# MCU025A_XDS110_MCU.net
KiCad netlist of a schematic drawn in Altium Designer
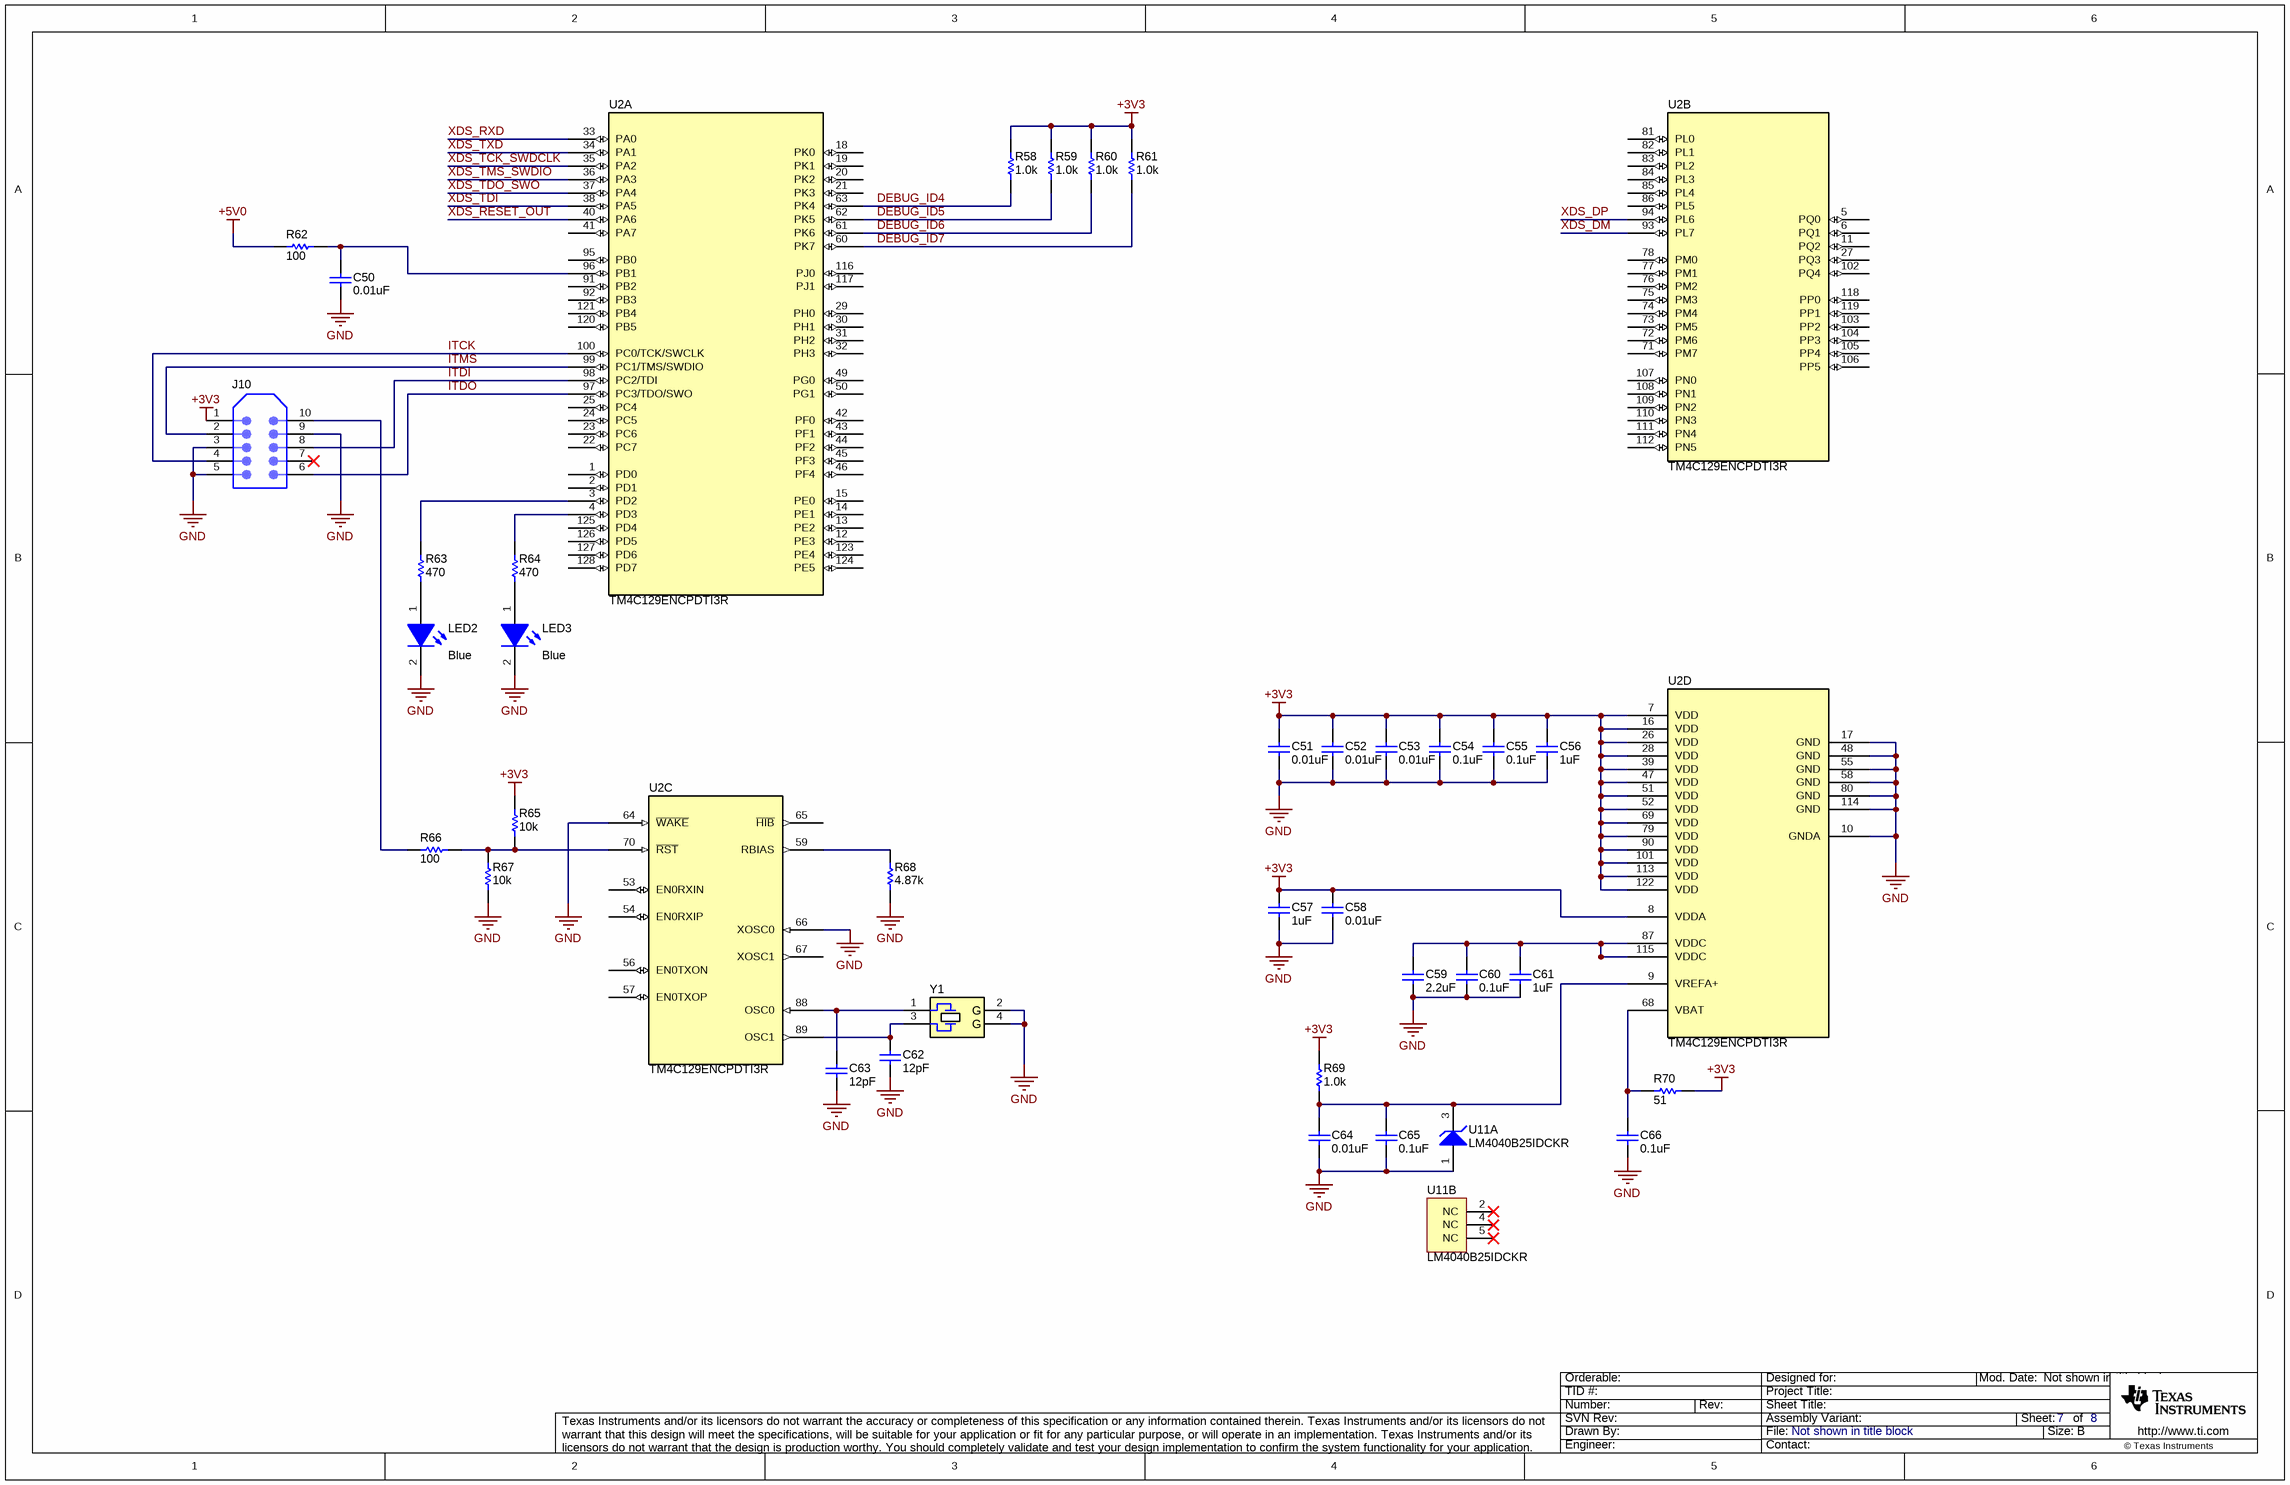
[diagram p0: MCU025A_XDS110_MCU.SchDoc]

(export (version "E")
  (design (tool "Eeschema 10.0.6"))
  (components
    (comp (ref "C50")
      (value "GRM155R71E103KA01D")
      (footprint "0402")
      (description "CAP, CERM, 0.01 uF, 25 V, +/- 10%, X7R, 0402")
      (fields
        (field (name "VALUEDISPLAYED") "0.01uF")
        (field (name "MANUFACTURER") "MuRata")
        (field (name "PUBLISHER") "Texas Instruments")
      )
      (libsource (lib "Altium Vault - TI") (part "Capacitor"))
    )
    (comp (ref "C51")
      (value "GRM155R71E103KA01D")
      (footprint "0402")
      (description "CAP, CERM, 0.01 uF, 25 V, +/- 10%, X7R, 0402")
      (fields
        (field (name "VALUEDISPLAYED") "0.01uF")
        (field (name "MANUFACTURER") "MuRata")
        (field (name "PUBLISHER") "Texas Instruments")
      )
      (libsource (lib "Altium Vault - TI") (part "Capacitor"))
    )
    (comp (ref "C52")
      (value "GRM155R71E103KA01D")
      (footprint "0402")
      (description "CAP, CERM, 0.01 uF, 25 V, +/- 10%, X7R, 0402")
      (fields
        (field (name "VALUEDISPLAYED") "0.01uF")
        (field (name "MANUFACTURER") "MuRata")
        (field (name "PUBLISHER") "Texas Instruments")
      )
      (libsource (lib "Altium Vault - TI") (part "Capacitor"))
    )
    (comp (ref "C53")
      (value "GRM155R71E103KA01D")
      (footprint "0402")
      (description "CAP, CERM, 0.01 uF, 25 V, +/- 10%, X7R, 0402")
      (fields
        (field (name "VALUEDISPLAYED") "0.01uF")
        (field (name "MANUFACTURER") "MuRata")
        (field (name "PUBLISHER") "Texas Instruments")
      )
      (libsource (lib "Altium Vault - TI") (part "Capacitor"))
    )
    (comp (ref "C54")
      (value "GRM155R70J104KA01D")
      (footprint "0402")
      (description "CAP, CERM, 0.1 uF, 6.3 V, +/- 10%, X7R, 0402")
      (fields
        (field (name "VALUEDISPLAYED") "0.1uF")
        (field (name "MANUFACTURER") "MuRata")
        (field (name "PUBLISHER") "Texas Instruments")
      )
      (libsource (lib "Altium Vault - TI") (part "Capacitor"))
    )
    (comp (ref "C55")
      (value "GRM155R70J104KA01D")
      (footprint "0402")
      (description "CAP, CERM, 0.1 uF, 6.3 V, +/- 10%, X7R, 0402")
      (fields
        (field (name "VALUEDISPLAYED") "0.1uF")
        (field (name "MANUFACTURER") "MuRata")
        (field (name "PUBLISHER") "Texas Instruments")
      )
      (libsource (lib "Altium Vault - TI") (part "Capacitor"))
    )
    (comp (ref "C56")
      (value "GRM155R61A105KE15D")
      (footprint "0402")
      (description "CAP, CERM, 1 uF, 10 V, +/- 10%, X5R, 0402")
      (fields
        (field (name "VALUEDISPLAYED") "1uF")
        (field (name "MANUFACTURER") "MuRata")
        (field (name "PUBLISHER") "Texas Instruments")
      )
      (libsource (lib "Altium Vault - TI") (part "Capacitor"))
    )
    (comp (ref "C57")
      (value "GRM155R61A105KE15D")
      (footprint "0402")
      (description "CAP, CERM, 1 uF, 10 V, +/- 10%, X5R, 0402")
      (fields
        (field (name "VALUEDISPLAYED") "1uF")
        (field (name "MANUFACTURER") "MuRata")
        (field (name "PUBLISHER") "Texas Instruments")
      )
      (libsource (lib "Altium Vault - TI") (part "Capacitor"))
    )
    (comp (ref "C58")
      (value "GRM155R71E103KA01D")
      (footprint "0402")
      (description "CAP, CERM, 0.01 uF, 25 V, +/- 10%, X7R, 0402")
      (fields
        (field (name "VALUEDISPLAYED") "0.01uF")
        (field (name "MANUFACTURER") "MuRata")
        (field (name "PUBLISHER") "Texas Instruments")
      )
      (libsource (lib "Altium Vault - TI") (part "Capacitor"))
    )
    (comp (ref "C59")
      (value "GRM155R60J225KE95D")
      (footprint "0402")
      (description "CAP, CERM, 2.2 uF, 6.3 V, +/- 10%, X5R, 0402")
      (fields
        (field (name "VALUEDISPLAYED") "2.2uF")
        (field (name "MANUFACTURER") "MuRata")
        (field (name "PUBLISHER") "Texas Instruments")
      )
      (libsource (lib "Altium Vault - TI") (part "Capacitor"))
    )
    (comp (ref "C60")
      (value "GRM155R70J104KA01D")
      (footprint "0402")
      (description "CAP, CERM, 0.1 uF, 6.3 V, +/- 10%, X7R, 0402")
      (fields
        (field (name "VALUEDISPLAYED") "0.1uF")
        (field (name "MANUFACTURER") "MuRata")
        (field (name "PUBLISHER") "Texas Instruments")
      )
      (libsource (lib "Altium Vault - TI") (part "Capacitor"))
    )
    (comp (ref "C61")
      (value "GRM155R61A105KE15D")
      (footprint "0402")
      (description "CAP, CERM, 1 uF, 10 V, +/- 10%, X5R, 0402")
      (fields
        (field (name "VALUEDISPLAYED") "1uF")
        (field (name "MANUFACTURER") "MuRata")
        (field (name "PUBLISHER") "Texas Instruments")
      )
      (libsource (lib "Altium Vault - TI") (part "Capacitor"))
    )
    (comp (ref "C62")
      (value "GRM1555C1H120JA01D")
      (footprint "0402")
      (description "CAP, CERM, 12 pF, 50 V, +/- 5%, C0G/NP0, 0402")
      (fields
        (field (name "VALUEDISPLAYED") "12pF")
        (field (name "MANUFACTURER") "MuRata")
        (field (name "PUBLISHER") "Texas Instruments")
      )
      (libsource (lib "Altium Vault - TI") (part "Capacitor"))
    )
    (comp (ref "C63")
      (value "GRM1555C1H120JA01D")
      (footprint "0402")
      (description "CAP, CERM, 12 pF, 50 V, +/- 5%, C0G/NP0, 0402")
      (fields
        (field (name "VALUEDISPLAYED") "12pF")
        (field (name "MANUFACTURER") "MuRata")
        (field (name "PUBLISHER") "Texas Instruments")
      )
      (libsource (lib "Altium Vault - TI") (part "Capacitor"))
    )
    (comp (ref "C64")
      (value "GRM155R71E103KA01D")
      (footprint "0402")
      (description "CAP, CERM, 0.01 uF, 25 V, +/- 10%, X7R, 0402")
      (fields
        (field (name "VALUEDISPLAYED") "0.01uF")
        (field (name "MANUFACTURER") "MuRata")
        (field (name "PUBLISHER") "Texas Instruments")
      )
      (libsource (lib "Altium Vault - TI") (part "Capacitor"))
    )
    (comp (ref "C65")
      (value "GRM155R70J104KA01D")
      (footprint "0402")
      (description "CAP, CERM, 0.1 uF, 6.3 V, +/- 10%, X7R, 0402")
      (fields
        (field (name "VALUEDISPLAYED") "0.1uF")
        (field (name "MANUFACTURER") "MuRata")
        (field (name "PUBLISHER") "Texas Instruments")
      )
      (libsource (lib "Altium Vault - TI") (part "Capacitor"))
    )
    (comp (ref "C66")
      (value "GRM155R70J104KA01D")
      (footprint "0402")
      (description "CAP, CERM, 0.1 uF, 6.3 V, +/- 10%, X7R, 0402")
      (fields
        (field (name "VALUEDISPLAYED") "0.1uF")
        (field (name "MANUFACTURER") "MuRata")
        (field (name "PUBLISHER") "Texas Instruments")
      )
      (libsource (lib "Altium Vault - TI") (part "Capacitor"))
    )
    (comp (ref "J10")
      (value "TC2050-IDC-NL-FP")
      (footprint "Tag_TC2050-NL")
      (description "Footprint for Tag-Connect TC2050 No-Legs cables")
      (fields (field (name "MANUFACTURER") "Tag-Connect") (field (name "PUBLISHER") "Texas Instruments"))
      (libsource (lib "Altium Vault - TI") (part "CMP-0075101-1"))
    )
    (comp (ref "LED2")
      (value "Blue")
      (footprint "LTST-C170TBKT_Blue")
      (description "LED, Blue, SMD")
      (fields
        (field (name "PARTNUMBER") "LTST-C170TBKT")
        (field (name "MANUFACTURER") "Lite-On")
        (field (name "PUBLISHER") "Texas Instruments")
      )
      (libsource (lib "Altium Vault - TI") (part "CMP-0002889-1"))
    )
    (comp (ref "LED3")
      (value "Blue")
      (footprint "LTST-C170TBKT_Blue")
      (description "LED, Blue, SMD")
      (fields
        (field (name "PARTNUMBER") "LTST-C170TBKT")
        (field (name "MANUFACTURER") "Lite-On")
        (field (name "PUBLISHER") "Texas Instruments")
      )
      (libsource (lib "Altium Vault - TI") (part "CMP-0002889-1"))
    )
    (comp (ref "R58")
      (value "CRCW04021K00JNED")
      (footprint "0402")
      (description "RES, 1.0 k, 5%, 0.063 W, AEC-Q200 Grade 0, 0402")
      (fields (field (name "MANUFACTURER") "Vishay-Dale") (field (name "VALUEDISPLAYED") "1.0k"))
      (libsource (lib "Altium Vault - TI") (part "Resistor"))
    )
    (comp (ref "R59")
      (value "CRCW04021K00JNED")
      (footprint "0402")
      (description "RES, 1.0 k, 5%, 0.063 W, AEC-Q200 Grade 0, 0402")
      (fields (field (name "MANUFACTURER") "Vishay-Dale") (field (name "VALUEDISPLAYED") "1.0k"))
      (libsource (lib "Altium Vault - TI") (part "Resistor"))
    )
    (comp (ref "R60")
      (value "CRCW04021K00JNED")
      (footprint "0402")
      (description "RES, 1.0 k, 5%, 0.063 W, AEC-Q200 Grade 0, 0402")
      (fields (field (name "MANUFACTURER") "Vishay-Dale") (field (name "VALUEDISPLAYED") "1.0k"))
      (libsource (lib "Altium Vault - TI") (part "Resistor"))
    )
    (comp (ref "R61")
      (value "CRCW04021K00JNED")
      (footprint "0402")
      (description "RES, 1.0 k, 5%, 0.063 W, AEC-Q200 Grade 0, 0402")
      (fields (field (name "MANUFACTURER") "Vishay-Dale") (field (name "VALUEDISPLAYED") "1.0k"))
      (libsource (lib "Altium Vault - TI") (part "Resistor"))
    )
    (comp (ref "R62")
      (value "CRCW0402100RJNED")
      (footprint "0402")
      (description "RES, 100, 5%, 0.063 W, AEC-Q200 Grade 0, 0402")
      (fields (field (name "VALUEDISPLAYED") "100") (field (name "MANUFACTURER") "Vishay-Dale"))
      (libsource (lib "Altium Vault - TI") (part "Resistor"))
    )
    (comp (ref "R63")
      (value "ERJ-2RKF4700X")
      (footprint "0402")
      (description "RES, 470, 1%, 0.1 W, AEC-Q200 Grade 0, 0402")
      (fields
        (field (name "VALUEDISPLAYED") "470")
        (field (name "MANUFACTURER") "Panasonic")
        (field (name "PUBLISHER") "Texas Instruments")
      )
      (libsource (lib "Altium Vault - TI") (part "Resistor"))
    )
    (comp (ref "R64")
      (value "ERJ-2RKF4700X")
      (footprint "0402")
      (description "RES, 470, 1%, 0.1 W, AEC-Q200 Grade 0, 0402")
      (fields
        (field (name "VALUEDISPLAYED") "470")
        (field (name "MANUFACTURER") "Panasonic")
        (field (name "PUBLISHER") "Texas Instruments")
      )
      (libsource (lib "Altium Vault - TI") (part "Resistor"))
    )
    (comp (ref "R65")
      (value "CRCW040210K0JNED")
      (footprint "0402")
      (description "RES, 10 k, 5%, 0.063 W, AEC-Q200 Grade 0, 0402")
      (fields (field (name "VALUEDISPLAYED") "10k") (field (name "MANUFACTURER") "Vishay-Dale"))
      (libsource (lib "Altium Vault - TI") (part "Resistor"))
    )
    (comp (ref "R66")
      (value "CRCW0402100RJNED")
      (footprint "0402")
      (description "RES, 100, 5%, 0.063 W, AEC-Q200 Grade 0, 0402")
      (fields (field (name "VALUEDISPLAYED") "100") (field (name "MANUFACTURER") "Vishay-Dale"))
      (libsource (lib "Altium Vault - TI") (part "Resistor"))
    )
    (comp (ref "R67")
      (value "CRCW040210K0JNED")
      (footprint "0402")
      (description "RES, 10 k, 5%, 0.063 W, AEC-Q200 Grade 0, 0402")
      (fields (field (name "VALUEDISPLAYED") "10k") (field (name "MANUFACTURER") "Vishay-Dale"))
      (libsource (lib "Altium Vault - TI") (part "Resistor"))
    )
    (comp (ref "R68")
      (value "CRCW04024K87FKED")
      (footprint "0402")
      (description "RES, 4.87 k, 1%, 0.063 W, AEC-Q200 Grade 0, 0402")
      (fields (field (name "VALUEDISPLAYED") "4.87k") (field (name "MANUFACTURER") "Vishay-Dale"))
      (libsource (lib "Altium Vault - TI") (part "Resistor"))
    )
    (comp (ref "R69")
      (value "CRCW04021K00JNED")
      (footprint "0402")
      (description "RES, 1.0 k, 5%, 0.063 W, AEC-Q200 Grade 0, 0402")
      (fields (field (name "VALUEDISPLAYED") "1.0k") (field (name "MANUFACTURER") "Vishay-Dale"))
      (libsource (lib "Altium Vault - TI") (part "Resistor"))
    )
    (comp (ref "R70")
      (value "CRCW040251R0JNED")
      (footprint "0402")
      (description "RES, 51, 5%, 0.063 W, AEC-Q200 Grade 0, 0402")
      (fields (field (name "VALUEDISPLAYED") "51") (field (name "MANUFACTURER") "Vishay-Dale"))
      (libsource (lib "Altium Vault - TI") (part "Resistor"))
    )
    (comp (ref "U2")
      (value "TM4C129ENCPDTI3R")
      (footprint "PDT0128A")
      (description "IoT enabled High performance 32-bit ARM(R) Cortex(R)-M4F based MCU, PDT0128A (TQFP-128)")
      (fields
        (field (name "ALTERNATE PARTNUMBER") "TM4C129ENCPDTI3")
        (field (name "MANUFACTURER") "Texas Instruments")
        (field (name "PUBLISHER") "Texas Instruments")
      )
      (libsource (lib "Altium Vault - TI") (part "CMP-0067512-2"))
    )
    (comp (ref "U11")
      (value "LM4040B25IDCKR")
      (footprint "DCK0005A_N")
      (fields (field (name "MANUFACTURER") "Texas Instruments") (field (name "PARTNUMBER") "LM4040B25IDCKR"))
      (libsource (lib "") (part "TI-LM4040B25DCK5_1"))
    )
    (comp (ref "Y1")
      (value "NX3225GA-16.000M-STD-CRG-1")
      (footprint "NDK_NX3225GA")
      (description "Crystal, 16 MHz, 8pF, SMD")
      (fields (field (name "MANUFACTURER") "NDK"))
      (libsource (lib "Altium Vault - TI") (part "XTAL_4P_13_G24"))
    )
  )
  (nets
    (net (code "1") (name "+3V3") (class "Default")
      (node (ref "C51") (pin "1") (pinfunction "1_1") (pintype "passive"))
      (node (ref "C52") (pin "1") (pinfunction "1_1") (pintype "passive"))
      (node (ref "C53") (pin "1") (pinfunction "1_1") (pintype "passive"))
      (node (ref "C54") (pin "1") (pinfunction "1_1") (pintype "passive"))
      (node (ref "C55") (pin "1") (pinfunction "1_1") (pintype "passive"))
      (node (ref "C56") (pin "1") (pinfunction "1_1") (pintype "passive"))
      (node (ref "C57") (pin "1") (pinfunction "1_1") (pintype "passive"))
      (node (ref "C58") (pin "1") (pinfunction "1_1") (pintype "passive"))
      (node (ref "J10") (pin "1") (pinfunction "1_1") (pintype "passive"))
      (node (ref "R58") (pin "2") (pinfunction "2_2") (pintype "passive"))
      (node (ref "R59") (pin "2") (pinfunction "2_2") (pintype "passive"))
      (node (ref "R60") (pin "2") (pinfunction "2_2") (pintype "passive"))
      (node (ref "R61") (pin "2") (pinfunction "2_2") (pintype "passive"))
      (node (ref "R65") (pin "2") (pinfunction "2_2") (pintype "passive"))
      (node (ref "R69") (pin "2") (pinfunction "2_2") (pintype "passive"))
      (node (ref "R70") (pin "2") (pinfunction "2_2") (pintype "passive"))
      (node (ref "U2") (pin "101") (pinfunction "VDD_101") (pintype "power_in"))
      (node (ref "U2") (pin "113") (pinfunction "VDD_113") (pintype "power_in"))
      (node (ref "U2") (pin "122") (pinfunction "VDD_122") (pintype "power_in"))
      (node (ref "U2") (pin "16") (pinfunction "VDD_16") (pintype "power_in"))
      (node (ref "U2") (pin "26") (pinfunction "VDD_26") (pintype "power_in"))
      (node (ref "U2") (pin "28") (pinfunction "VDD_28") (pintype "power_in"))
      (node (ref "U2") (pin "39") (pinfunction "VDD_39") (pintype "power_in"))
      (node (ref "U2") (pin "47") (pinfunction "VDD_47") (pintype "power_in"))
      (node (ref "U2") (pin "51") (pinfunction "VDD_51") (pintype "power_in"))
      (node (ref "U2") (pin "52") (pinfunction "VDD_52") (pintype "power_in"))
      (node (ref "U2") (pin "69") (pinfunction "VDD_69") (pintype "power_in"))
      (node (ref "U2") (pin "7") (pinfunction "VDD_7") (pintype "power_in"))
      (node (ref "U2") (pin "79") (pinfunction "VDD_79") (pintype "power_in"))
      (node (ref "U2") (pin "8") (pinfunction "VDDA_8") (pintype "power_in"))
      (node (ref "U2") (pin "90") (pinfunction "VDD_90") (pintype "power_in"))
    )
    (net (code "2") (name "+5V0") (class "Default")
      (node (ref "R62") (pin "1") (pinfunction "1_1") (pintype "passive"))
    )
    (net (code "3") (name "/DEBUG_ID4") (class "Default")
      (node (ref "R58") (pin "1") (pinfunction "1_1") (pintype "passive"))
      (node (ref "U2") (pin "63") (pinfunction "PK4_63") (pintype "bidirectional"))
    )
    (net (code "4") (name "/DEBUG_ID5") (class "Default")
      (node (ref "R59") (pin "1") (pinfunction "1_1") (pintype "passive"))
      (node (ref "U2") (pin "62") (pinfunction "PK5_62") (pintype "bidirectional"))
    )
    (net (code "5") (name "/DEBUG_ID6") (class "Default")
      (node (ref "R60") (pin "1") (pinfunction "1_1") (pintype "passive"))
      (node (ref "U2") (pin "61") (pinfunction "PK6_61") (pintype "bidirectional"))
    )
    (net (code "6") (name "/DEBUG_ID7") (class "Default")
      (node (ref "R61") (pin "1") (pinfunction "1_1") (pintype "passive"))
      (node (ref "U2") (pin "60") (pinfunction "PK7_60") (pintype "bidirectional"))
    )
    (net (code "7") (name "/ITCK") (class "Default")
      (node (ref "J10") (pin "4") (pinfunction "4_4") (pintype "passive"))
      (node (ref "U2") (pin "100") (pinfunction "PC0/TCK/SWCLK_100") (pintype "bidirectional"))
    )
    (net (code "8") (name "/ITDI") (class "Default")
      (node (ref "J10") (pin "8") (pinfunction "8_8") (pintype "passive"))
      (node (ref "U2") (pin "98") (pinfunction "PC2/TDI_98") (pintype "bidirectional"))
    )
    (net (code "9") (name "/ITDO") (class "Default")
      (node (ref "J10") (pin "6") (pinfunction "6_6") (pintype "passive"))
      (node (ref "U2") (pin "97") (pinfunction "PC3/TDO/SWO_97") (pintype "bidirectional"))
    )
    (net (code "10") (name "/ITMS") (class "Default")
      (node (ref "J10") (pin "2") (pinfunction "2_2") (pintype "passive"))
      (node (ref "U2") (pin "99") (pinfunction "PC1/TMS/SWDIO_99") (pintype "bidirectional"))
    )
    (net (code "11") (name "/XDS_DM") (class "Default")
      (node (ref "U2") (pin "93") (pinfunction "PL7_93") (pintype "bidirectional"))
    )
    (net (code "12") (name "/XDS_DP") (class "Default")
      (node (ref "U2") (pin "94") (pinfunction "PL6_94") (pintype "bidirectional"))
    )
    (net (code "13") (name "/XDS_RESET_OUT") (class "Default")
      (node (ref "U2") (pin "40") (pinfunction "PA6_40") (pintype "bidirectional"))
    )
    (net (code "14") (name "/XDS_RXD") (class "Default")
      (node (ref "U2") (pin "33") (pinfunction "PA0_33") (pintype "bidirectional"))
    )
    (net (code "15") (name "/XDS_TCK_SWDCLK") (class "Default")
      (node (ref "U2") (pin "35") (pinfunction "PA2_35") (pintype "bidirectional"))
    )
    (net (code "16") (name "/XDS_TDI") (class "Default")
      (node (ref "U2") (pin "38") (pinfunction "PA5_38") (pintype "bidirectional"))
    )
    (net (code "17") (name "/XDS_TDO_SWO") (class "Default")
      (node (ref "U2") (pin "37") (pinfunction "PA4_37") (pintype "bidirectional"))
    )
    (net (code "18") (name "/XDS_TMS_SWDIO") (class "Default")
      (node (ref "U2") (pin "36") (pinfunction "PA3_36") (pintype "bidirectional"))
    )
    (net (code "19") (name "/XDS_TXD") (class "Default")
      (node (ref "U2") (pin "34") (pinfunction "PA1_34") (pintype "bidirectional"))
    )
    (net (code "20") (name "GND") (class "Default")
      (node (ref "C50") (pin "2") (pinfunction "2_2") (pintype "passive"))
      (node (ref "C51") (pin "2") (pinfunction "2_2") (pintype "passive"))
      (node (ref "C52") (pin "2") (pinfunction "2_2") (pintype "passive"))
      (node (ref "C53") (pin "2") (pinfunction "2_2") (pintype "passive"))
      (node (ref "C54") (pin "2") (pinfunction "2_2") (pintype "passive"))
      (node (ref "C55") (pin "2") (pinfunction "2_2") (pintype "passive"))
      (node (ref "C56") (pin "2") (pinfunction "2_2") (pintype "passive"))
      (node (ref "C57") (pin "2") (pinfunction "2_2") (pintype "passive"))
      (node (ref "C58") (pin "2") (pinfunction "2_2") (pintype "passive"))
      (node (ref "C59") (pin "2") (pinfunction "2_2") (pintype "passive"))
      (node (ref "C60") (pin "2") (pinfunction "2_2") (pintype "passive"))
      (node (ref "C61") (pin "2") (pinfunction "2_2") (pintype "passive"))
      (node (ref "C62") (pin "2") (pinfunction "2_2") (pintype "passive"))
      (node (ref "C63") (pin "2") (pinfunction "2_2") (pintype "passive"))
      (node (ref "C64") (pin "2") (pinfunction "2_2") (pintype "passive"))
      (node (ref "C65") (pin "2") (pinfunction "2_2") (pintype "passive"))
      (node (ref "C66") (pin "2") (pinfunction "2_2") (pintype "passive"))
      (node (ref "J10") (pin "3") (pinfunction "3_3") (pintype "passive"))
      (node (ref "J10") (pin "5") (pinfunction "5_5") (pintype "passive"))
      (node (ref "J10") (pin "9") (pinfunction "9_9") (pintype "passive"))
      (node (ref "LED2") (pin "2") (pinfunction "K_2") (pintype "passive"))
      (node (ref "LED3") (pin "2") (pinfunction "K_2") (pintype "passive"))
      (node (ref "R67") (pin "1") (pinfunction "1_1") (pintype "passive"))
      (node (ref "R68") (pin "1") (pinfunction "1_1") (pintype "passive"))
      (node (ref "U11") (pin "1") (pinfunction "ANODE_1") (pintype "passive"))
      (node (ref "U2") (pin "10") (pinfunction "GNDA_10") (pintype "power_in"))
      (node (ref "U2") (pin "114") (pinfunction "GND_114") (pintype "power_in"))
      (node (ref "U2") (pin "17") (pinfunction "GND_17") (pintype "power_in"))
      (node (ref "U2") (pin "48") (pinfunction "GND_48") (pintype "power_in"))
      (node (ref "U2") (pin "55") (pinfunction "GND_55") (pintype "power_in"))
      (node (ref "U2") (pin "58") (pinfunction "GND_58") (pintype "power_in"))
      (node (ref "U2") (pin "64") (pinfunction "WAKE_64") (pintype "input"))
      (node (ref "U2") (pin "66") (pinfunction "XOSC0_66") (pintype "input"))
      (node (ref "U2") (pin "80") (pinfunction "GND_80") (pintype "power_in"))
      (node (ref "Y1") (pin "2") (pinfunction "GND_2") (pintype "power_in"))
      (node (ref "Y1") (pin "4") (pinfunction "GND_4") (pintype "power_in"))
    )
    (net (code "21") (name "Net-(C59-Pad1)") (class "Default")
      (node (ref "C59") (pin "1") (pinfunction "1_1") (pintype "passive"))
      (node (ref "C60") (pin "1") (pinfunction "1_1") (pintype "passive"))
      (node (ref "C61") (pin "1") (pinfunction "1_1") (pintype "passive"))
      (node (ref "U2") (pin "115") (pinfunction "VDDC_115") (pintype "power_in"))
      (node (ref "U2") (pin "87") (pinfunction "VDDC_87") (pintype "power_in"))
    )
    (net (code "22") (name "Net-(J10-Pad10)") (class "Default")
      (node (ref "J10") (pin "10") (pinfunction "10_10") (pintype "passive"))
      (node (ref "R66") (pin "1") (pinfunction "1_1") (pintype "passive"))
    )
    (net (code "23") (name "Net-(LED2-A)") (class "Default")
      (node (ref "LED2") (pin "1") (pinfunction "A_1") (pintype "passive"))
      (node (ref "R63") (pin "1") (pinfunction "1_1") (pintype "passive"))
    )
    (net (code "24") (name "Net-(LED3-A)") (class "Default")
      (node (ref "LED3") (pin "1") (pinfunction "A_1") (pintype "passive"))
      (node (ref "R64") (pin "1") (pinfunction "1_1") (pintype "passive"))
    )
    (net (code "25") (name "Net-(U2A-PB1)") (class "Default")
      (node (ref "C50") (pin "1") (pinfunction "1_1") (pintype "passive"))
      (node (ref "R62") (pin "2") (pinfunction "2_2") (pintype "passive"))
      (node (ref "U2") (pin "96") (pinfunction "PB1_96") (pintype "bidirectional"))
    )
    (net (code "26") (name "Net-(U2A-PD2)") (class "Default")
      (node (ref "R63") (pin "2") (pinfunction "2_2") (pintype "passive"))
      (node (ref "U2") (pin "3") (pinfunction "PD2_3") (pintype "bidirectional"))
    )
    (net (code "27") (name "Net-(U2A-PD3)") (class "Default")
      (node (ref "R64") (pin "2") (pinfunction "2_2") (pintype "passive"))
      (node (ref "U2") (pin "4") (pinfunction "PD3_4") (pintype "bidirectional"))
    )
    (net (code "28") (name "Net-(U2C-OSC0)") (class "Default")
      (node (ref "C63") (pin "1") (pinfunction "1_1") (pintype "passive"))
      (node (ref "U2") (pin "88") (pinfunction "OSC0_88") (pintype "input"))
      (node (ref "Y1") (pin "1") (pinfunction "1_1") (pintype "passive"))
    )
    (net (code "29") (name "Net-(U2C-OSC1)") (class "Default")
      (node (ref "C62") (pin "1") (pinfunction "1_1") (pintype "passive"))
      (node (ref "U2") (pin "89") (pinfunction "OSC1_89") (pintype "output"))
      (node (ref "Y1") (pin "3") (pinfunction "3_3") (pintype "passive"))
    )
    (net (code "30") (name "Net-(U2C-RBIAS)") (class "Default")
      (node (ref "R68") (pin "2") (pinfunction "2_2") (pintype "passive"))
      (node (ref "U2") (pin "59") (pinfunction "RBIAS_59") (pintype "output"))
    )
    (net (code "31") (name "Net-(U2C-RST)") (class "Default")
      (node (ref "R65") (pin "1") (pinfunction "1_1") (pintype "passive"))
      (node (ref "R66") (pin "2") (pinfunction "2_2") (pintype "passive"))
      (node (ref "R67") (pin "2") (pinfunction "2_2") (pintype "passive"))
      (node (ref "U2") (pin "70") (pinfunction "RST_70") (pintype "input"))
    )
    (net (code "32") (name "Net-(U2D-VBAT)") (class "Default")
      (node (ref "C66") (pin "1") (pinfunction "1_1") (pintype "passive"))
      (node (ref "R70") (pin "1") (pinfunction "1_1") (pintype "passive"))
      (node (ref "U2") (pin "68") (pinfunction "VBAT_68") (pintype "power_in"))
    )
    (net (code "33") (name "Net-(U11A-CATHODE)") (class "Default")
      (node (ref "C64") (pin "1") (pinfunction "1_1") (pintype "passive"))
      (node (ref "C65") (pin "1") (pinfunction "1_1") (pintype "passive"))
      (node (ref "R69") (pin "1") (pinfunction "1_1") (pintype "passive"))
      (node (ref "U11") (pin "3") (pinfunction "CATHODE_3") (pintype "passive"))
      (node (ref "U2") (pin "9") (pinfunction "VREFA+_9") (pintype "power_in"))
    )
    (net (code "34") (name "unconnected-(J10-Pad7)") (class "Default")
      (node (ref "J10") (pin "7") (pinfunction "7_7") (pintype "passive+no_connect"))
    )
    (net (code "35") (name "unconnected-(U2A-PA7-Pad41)") (class "Default")
      (node (ref "U2") (pin "41") (pinfunction "PA7_41") (pintype "bidirectional"))
    )
    (net (code "36") (name "unconnected-(U2A-PB0-Pad95)") (class "Default")
      (node (ref "U2") (pin "95") (pinfunction "PB0_95") (pintype "bidirectional"))
    )
    (net (code "37") (name "unconnected-(U2A-PB2-Pad91)") (class "Default")
      (node (ref "U2") (pin "91") (pinfunction "PB2_91") (pintype "bidirectional"))
    )
    (net (code "38") (name "unconnected-(U2A-PB3-Pad92)") (class "Default")
      (node (ref "U2") (pin "92") (pinfunction "PB3_92") (pintype "bidirectional"))
    )
    (net (code "39") (name "unconnected-(U2A-PB4-Pad121)") (class "Default")
      (node (ref "U2") (pin "121") (pinfunction "PB4_121") (pintype "bidirectional"))
    )
    (net (code "40") (name "unconnected-(U2A-PB5-Pad120)") (class "Default")
      (node (ref "U2") (pin "120") (pinfunction "PB5_120") (pintype "bidirectional"))
    )
    (net (code "41") (name "unconnected-(U2A-PC4-Pad25)") (class "Default")
      (node (ref "U2") (pin "25") (pinfunction "PC4_25") (pintype "bidirectional"))
    )
    (net (code "42") (name "unconnected-(U2A-PC5-Pad24)") (class "Default")
      (node (ref "U2") (pin "24") (pinfunction "PC5_24") (pintype "bidirectional"))
    )
    (net (code "43") (name "unconnected-(U2A-PC6-Pad23)") (class "Default")
      (node (ref "U2") (pin "23") (pinfunction "PC6_23") (pintype "bidirectional"))
    )
    (net (code "44") (name "unconnected-(U2A-PC7-Pad22)") (class "Default")
      (node (ref "U2") (pin "22") (pinfunction "PC7_22") (pintype "bidirectional"))
    )
    (net (code "45") (name "unconnected-(U2A-PD0-Pad1)") (class "Default")
      (node (ref "U2") (pin "1") (pinfunction "PD0_1") (pintype "bidirectional"))
    )
    (net (code "46") (name "unconnected-(U2A-PD1-Pad2)") (class "Default")
      (node (ref "U2") (pin "2") (pinfunction "PD1_2") (pintype "bidirectional"))
    )
    (net (code "47") (name "unconnected-(U2A-PD4-Pad125)") (class "Default")
      (node (ref "U2") (pin "125") (pinfunction "PD4_125") (pintype "bidirectional"))
    )
    (net (code "48") (name "unconnected-(U2A-PD5-Pad126)") (class "Default")
      (node (ref "U2") (pin "126") (pinfunction "PD5_126") (pintype "bidirectional"))
    )
    (net (code "49") (name "unconnected-(U2A-PD6-Pad127)") (class "Default")
      (node (ref "U2") (pin "127") (pinfunction "PD6_127") (pintype "bidirectional"))
    )
    (net (code "50") (name "unconnected-(U2A-PD7-Pad128)") (class "Default")
      (node (ref "U2") (pin "128") (pinfunction "PD7_128") (pintype "bidirectional"))
    )
    (net (code "51") (name "unconnected-(U2A-PE0-Pad15)") (class "Default")
      (node (ref "U2") (pin "15") (pinfunction "PE0_15") (pintype "bidirectional"))
    )
    (net (code "52") (name "unconnected-(U2A-PE1-Pad14)") (class "Default")
      (node (ref "U2") (pin "14") (pinfunction "PE1_14") (pintype "bidirectional"))
    )
    (net (code "53") (name "unconnected-(U2A-PE2-Pad13)") (class "Default")
      (node (ref "U2") (pin "13") (pinfunction "PE2_13") (pintype "bidirectional"))
    )
    (net (code "54") (name "unconnected-(U2A-PE3-Pad12)") (class "Default")
      (node (ref "U2") (pin "12") (pinfunction "PE3_12") (pintype "bidirectional"))
    )
    (net (code "55") (name "unconnected-(U2A-PE4-Pad123)") (class "Default")
      (node (ref "U2") (pin "123") (pinfunction "PE4_123") (pintype "bidirectional"))
    )
    (net (code "56") (name "unconnected-(U2A-PE5-Pad124)") (class "Default")
      (node (ref "U2") (pin "124") (pinfunction "PE5_124") (pintype "bidirectional"))
    )
    (net (code "57") (name "unconnected-(U2A-PF0-Pad42)") (class "Default")
      (node (ref "U2") (pin "42") (pinfunction "PF0_42") (pintype "bidirectional"))
    )
    (net (code "58") (name "unconnected-(U2A-PF1-Pad43)") (class "Default")
      (node (ref "U2") (pin "43") (pinfunction "PF1_43") (pintype "bidirectional"))
    )
    (net (code "59") (name "unconnected-(U2A-PF2-Pad44)") (class "Default")
      (node (ref "U2") (pin "44") (pinfunction "PF2_44") (pintype "bidirectional"))
    )
    (net (code "60") (name "unconnected-(U2A-PF3-Pad45)") (class "Default")
      (node (ref "U2") (pin "45") (pinfunction "PF3_45") (pintype "bidirectional"))
    )
    (net (code "61") (name "unconnected-(U2A-PF4-Pad46)") (class "Default")
      (node (ref "U2") (pin "46") (pinfunction "PF4_46") (pintype "bidirectional"))
    )
    (net (code "62") (name "unconnected-(U2A-PG0-Pad49)") (class "Default")
      (node (ref "U2") (pin "49") (pinfunction "PG0_49") (pintype "bidirectional"))
    )
    (net (code "63") (name "unconnected-(U2A-PG1-Pad50)") (class "Default")
      (node (ref "U2") (pin "50") (pinfunction "PG1_50") (pintype "bidirectional"))
    )
    (net (code "64") (name "unconnected-(U2A-PH0-Pad29)") (class "Default")
      (node (ref "U2") (pin "29") (pinfunction "PH0_29") (pintype "bidirectional"))
    )
    (net (code "65") (name "unconnected-(U2A-PH1-Pad30)") (class "Default")
      (node (ref "U2") (pin "30") (pinfunction "PH1_30") (pintype "bidirectional"))
    )
    (net (code "66") (name "unconnected-(U2A-PH2-Pad31)") (class "Default")
      (node (ref "U2") (pin "31") (pinfunction "PH2_31") (pintype "bidirectional"))
    )
    (net (code "67") (name "unconnected-(U2A-PH3-Pad32)") (class "Default")
      (node (ref "U2") (pin "32") (pinfunction "PH3_32") (pintype "bidirectional"))
    )
    (net (code "68") (name "unconnected-(U2A-PJ0-Pad116)") (class "Default")
      (node (ref "U2") (pin "116") (pinfunction "PJ0_116") (pintype "bidirectional"))
    )
    (net (code "69") (name "unconnected-(U2A-PJ1-Pad117)") (class "Default")
      (node (ref "U2") (pin "117") (pinfunction "PJ1_117") (pintype "bidirectional"))
    )
    (net (code "70") (name "unconnected-(U2A-PK0-Pad18)") (class "Default")
      (node (ref "U2") (pin "18") (pinfunction "PK0_18") (pintype "bidirectional"))
    )
    (net (code "71") (name "unconnected-(U2A-PK1-Pad19)") (class "Default")
      (node (ref "U2") (pin "19") (pinfunction "PK1_19") (pintype "bidirectional"))
    )
    (net (code "72") (name "unconnected-(U2A-PK2-Pad20)") (class "Default")
      (node (ref "U2") (pin "20") (pinfunction "PK2_20") (pintype "bidirectional"))
    )
    (net (code "73") (name "unconnected-(U2A-PK3-Pad21)") (class "Default")
      (node (ref "U2") (pin "21") (pinfunction "PK3_21") (pintype "bidirectional"))
    )
    (net (code "74") (name "unconnected-(U2B-PL0-Pad81)") (class "Default")
      (node (ref "U2") (pin "81") (pinfunction "PL0_81") (pintype "bidirectional"))
    )
    (net (code "75") (name "unconnected-(U2B-PL1-Pad82)") (class "Default")
      (node (ref "U2") (pin "82") (pinfunction "PL1_82") (pintype "bidirectional"))
    )
    (net (code "76") (name "unconnected-(U2B-PL2-Pad83)") (class "Default")
      (node (ref "U2") (pin "83") (pinfunction "PL2_83") (pintype "bidirectional"))
    )
    (net (code "77") (name "unconnected-(U2B-PL3-Pad84)") (class "Default")
      (node (ref "U2") (pin "84") (pinfunction "PL3_84") (pintype "bidirectional"))
    )
    (net (code "78") (name "unconnected-(U2B-PL4-Pad85)") (class "Default")
      (node (ref "U2") (pin "85") (pinfunction "PL4_85") (pintype "bidirectional"))
    )
    (net (code "79") (name "unconnected-(U2B-PL5-Pad86)") (class "Default")
      (node (ref "U2") (pin "86") (pinfunction "PL5_86") (pintype "bidirectional"))
    )
    (net (code "80") (name "unconnected-(U2B-PM0-Pad78)") (class "Default")
      (node (ref "U2") (pin "78") (pinfunction "PM0_78") (pintype "bidirectional"))
    )
    (net (code "81") (name "unconnected-(U2B-PM1-Pad77)") (class "Default")
      (node (ref "U2") (pin "77") (pinfunction "PM1_77") (pintype "bidirectional"))
    )
    (net (code "82") (name "unconnected-(U2B-PM2-Pad76)") (class "Default")
      (node (ref "U2") (pin "76") (pinfunction "PM2_76") (pintype "bidirectional"))
    )
    (net (code "83") (name "unconnected-(U2B-PM3-Pad75)") (class "Default")
      (node (ref "U2") (pin "75") (pinfunction "PM3_75") (pintype "bidirectional"))
    )
    (net (code "84") (name "unconnected-(U2B-PM4-Pad74)") (class "Default")
      (node (ref "U2") (pin "74") (pinfunction "PM4_74") (pintype "bidirectional"))
    )
    (net (code "85") (name "unconnected-(U2B-PM5-Pad73)") (class "Default")
      (node (ref "U2") (pin "73") (pinfunction "PM5_73") (pintype "bidirectional"))
    )
    (net (code "86") (name "unconnected-(U2B-PM6-Pad72)") (class "Default")
      (node (ref "U2") (pin "72") (pinfunction "PM6_72") (pintype "bidirectional"))
    )
    (net (code "87") (name "unconnected-(U2B-PM7-Pad71)") (class "Default")
      (node (ref "U2") (pin "71") (pinfunction "PM7_71") (pintype "bidirectional"))
    )
    (net (code "88") (name "unconnected-(U2B-PN0-Pad107)") (class "Default")
      (node (ref "U2") (pin "107") (pinfunction "PN0_107") (pintype "bidirectional"))
    )
    (net (code "89") (name "unconnected-(U2B-PN1-Pad108)") (class "Default")
      (node (ref "U2") (pin "108") (pinfunction "PN1_108") (pintype "bidirectional"))
    )
    (net (code "90") (name "unconnected-(U2B-PN2-Pad109)") (class "Default")
      (node (ref "U2") (pin "109") (pinfunction "PN2_109") (pintype "bidirectional"))
    )
    (net (code "91") (name "unconnected-(U2B-PN3-Pad110)") (class "Default")
      (node (ref "U2") (pin "110") (pinfunction "PN3_110") (pintype "bidirectional"))
    )
    (net (code "92") (name "unconnected-(U2B-PN4-Pad111)") (class "Default")
      (node (ref "U2") (pin "111") (pinfunction "PN4_111") (pintype "bidirectional"))
    )
    (net (code "93") (name "unconnected-(U2B-PN5-Pad112)") (class "Default")
      (node (ref "U2") (pin "112") (pinfunction "PN5_112") (pintype "bidirectional"))
    )
    (net (code "94") (name "unconnected-(U2B-PP0-Pad118)") (class "Default")
      (node (ref "U2") (pin "118") (pinfunction "PP0_118") (pintype "bidirectional"))
    )
    (net (code "95") (name "unconnected-(U2B-PP1-Pad119)") (class "Default")
      (node (ref "U2") (pin "119") (pinfunction "PP1_119") (pintype "bidirectional"))
    )
    (net (code "96") (name "unconnected-(U2B-PP2-Pad103)") (class "Default")
      (node (ref "U2") (pin "103") (pinfunction "PP2_103") (pintype "bidirectional"))
    )
    (net (code "97") (name "unconnected-(U2B-PP3-Pad104)") (class "Default")
      (node (ref "U2") (pin "104") (pinfunction "PP3_104") (pintype "bidirectional"))
    )
    (net (code "98") (name "unconnected-(U2B-PP4-Pad105)") (class "Default")
      (node (ref "U2") (pin "105") (pinfunction "PP4_105") (pintype "bidirectional"))
    )
    (net (code "99") (name "unconnected-(U2B-PP5-Pad106)") (class "Default")
      (node (ref "U2") (pin "106") (pinfunction "PP5_106") (pintype "bidirectional"))
    )
    (net (code "100") (name "unconnected-(U2B-PQ0-Pad5)") (class "Default")
      (node (ref "U2") (pin "5") (pinfunction "PQ0_5") (pintype "bidirectional"))
    )
    (net (code "101") (name "unconnected-(U2B-PQ1-Pad6)") (class "Default")
      (node (ref "U2") (pin "6") (pinfunction "PQ1_6") (pintype "bidirectional"))
    )
    (net (code "102") (name "unconnected-(U2B-PQ2-Pad11)") (class "Default")
      (node (ref "U2") (pin "11") (pinfunction "PQ2_11") (pintype "bidirectional"))
    )
    (net (code "103") (name "unconnected-(U2B-PQ3-Pad27)") (class "Default")
      (node (ref "U2") (pin "27") (pinfunction "PQ3_27") (pintype "bidirectional"))
    )
    (net (code "104") (name "unconnected-(U2B-PQ4-Pad102)") (class "Default")
      (node (ref "U2") (pin "102") (pinfunction "PQ4_102") (pintype "bidirectional"))
    )
    (net (code "105") (name "unconnected-(U2C-EN0RXIN-Pad53)") (class "Default")
      (node (ref "U2") (pin "53") (pinfunction "EN0RXIN_53") (pintype "bidirectional"))
    )
    (net (code "106") (name "unconnected-(U2C-EN0RXIP-Pad54)") (class "Default")
      (node (ref "U2") (pin "54") (pinfunction "EN0RXIP_54") (pintype "bidirectional"))
    )
    (net (code "107") (name "unconnected-(U2C-EN0TXON-Pad56)") (class "Default")
      (node (ref "U2") (pin "56") (pinfunction "EN0TXON_56") (pintype "bidirectional"))
    )
    (net (code "108") (name "unconnected-(U2C-EN0TXOP-Pad57)") (class "Default")
      (node (ref "U2") (pin "57") (pinfunction "EN0TXOP_57") (pintype "bidirectional"))
    )
    (net (code "109") (name "unconnected-(U2C-HIB-Pad65)") (class "Default")
      (node (ref "U2") (pin "65") (pinfunction "HIB_65") (pintype "output"))
    )
    (net (code "110") (name "unconnected-(U2C-XOSC1-Pad67)") (class "Default")
      (node (ref "U2") (pin "67") (pinfunction "XOSC1_67") (pintype "output"))
    )
    (net (code "111") (name "unconnected-(U11B-NC-Pad2)") (class "Default")
      (node (ref "U11") (pin "2") (pinfunction "NC_2") (pintype "passive+no_connect"))
    )
    (net (code "112") (name "unconnected-(U11B-NC-Pad4)") (class "Default")
      (node (ref "U11") (pin "4") (pinfunction "NC_4") (pintype "passive+no_connect"))
    )
    (net (code "113") (name "unconnected-(U11B-NC-Pad5)") (class "Default")
      (node (ref "U11") (pin "5") (pinfunction "NC_5") (pintype "passive+no_connect"))
    )
  )
)
